# Circuito_Tappingduino_3_Final_-_Conexion.net
KiCad netlist of a schematic drawn in EAGLE
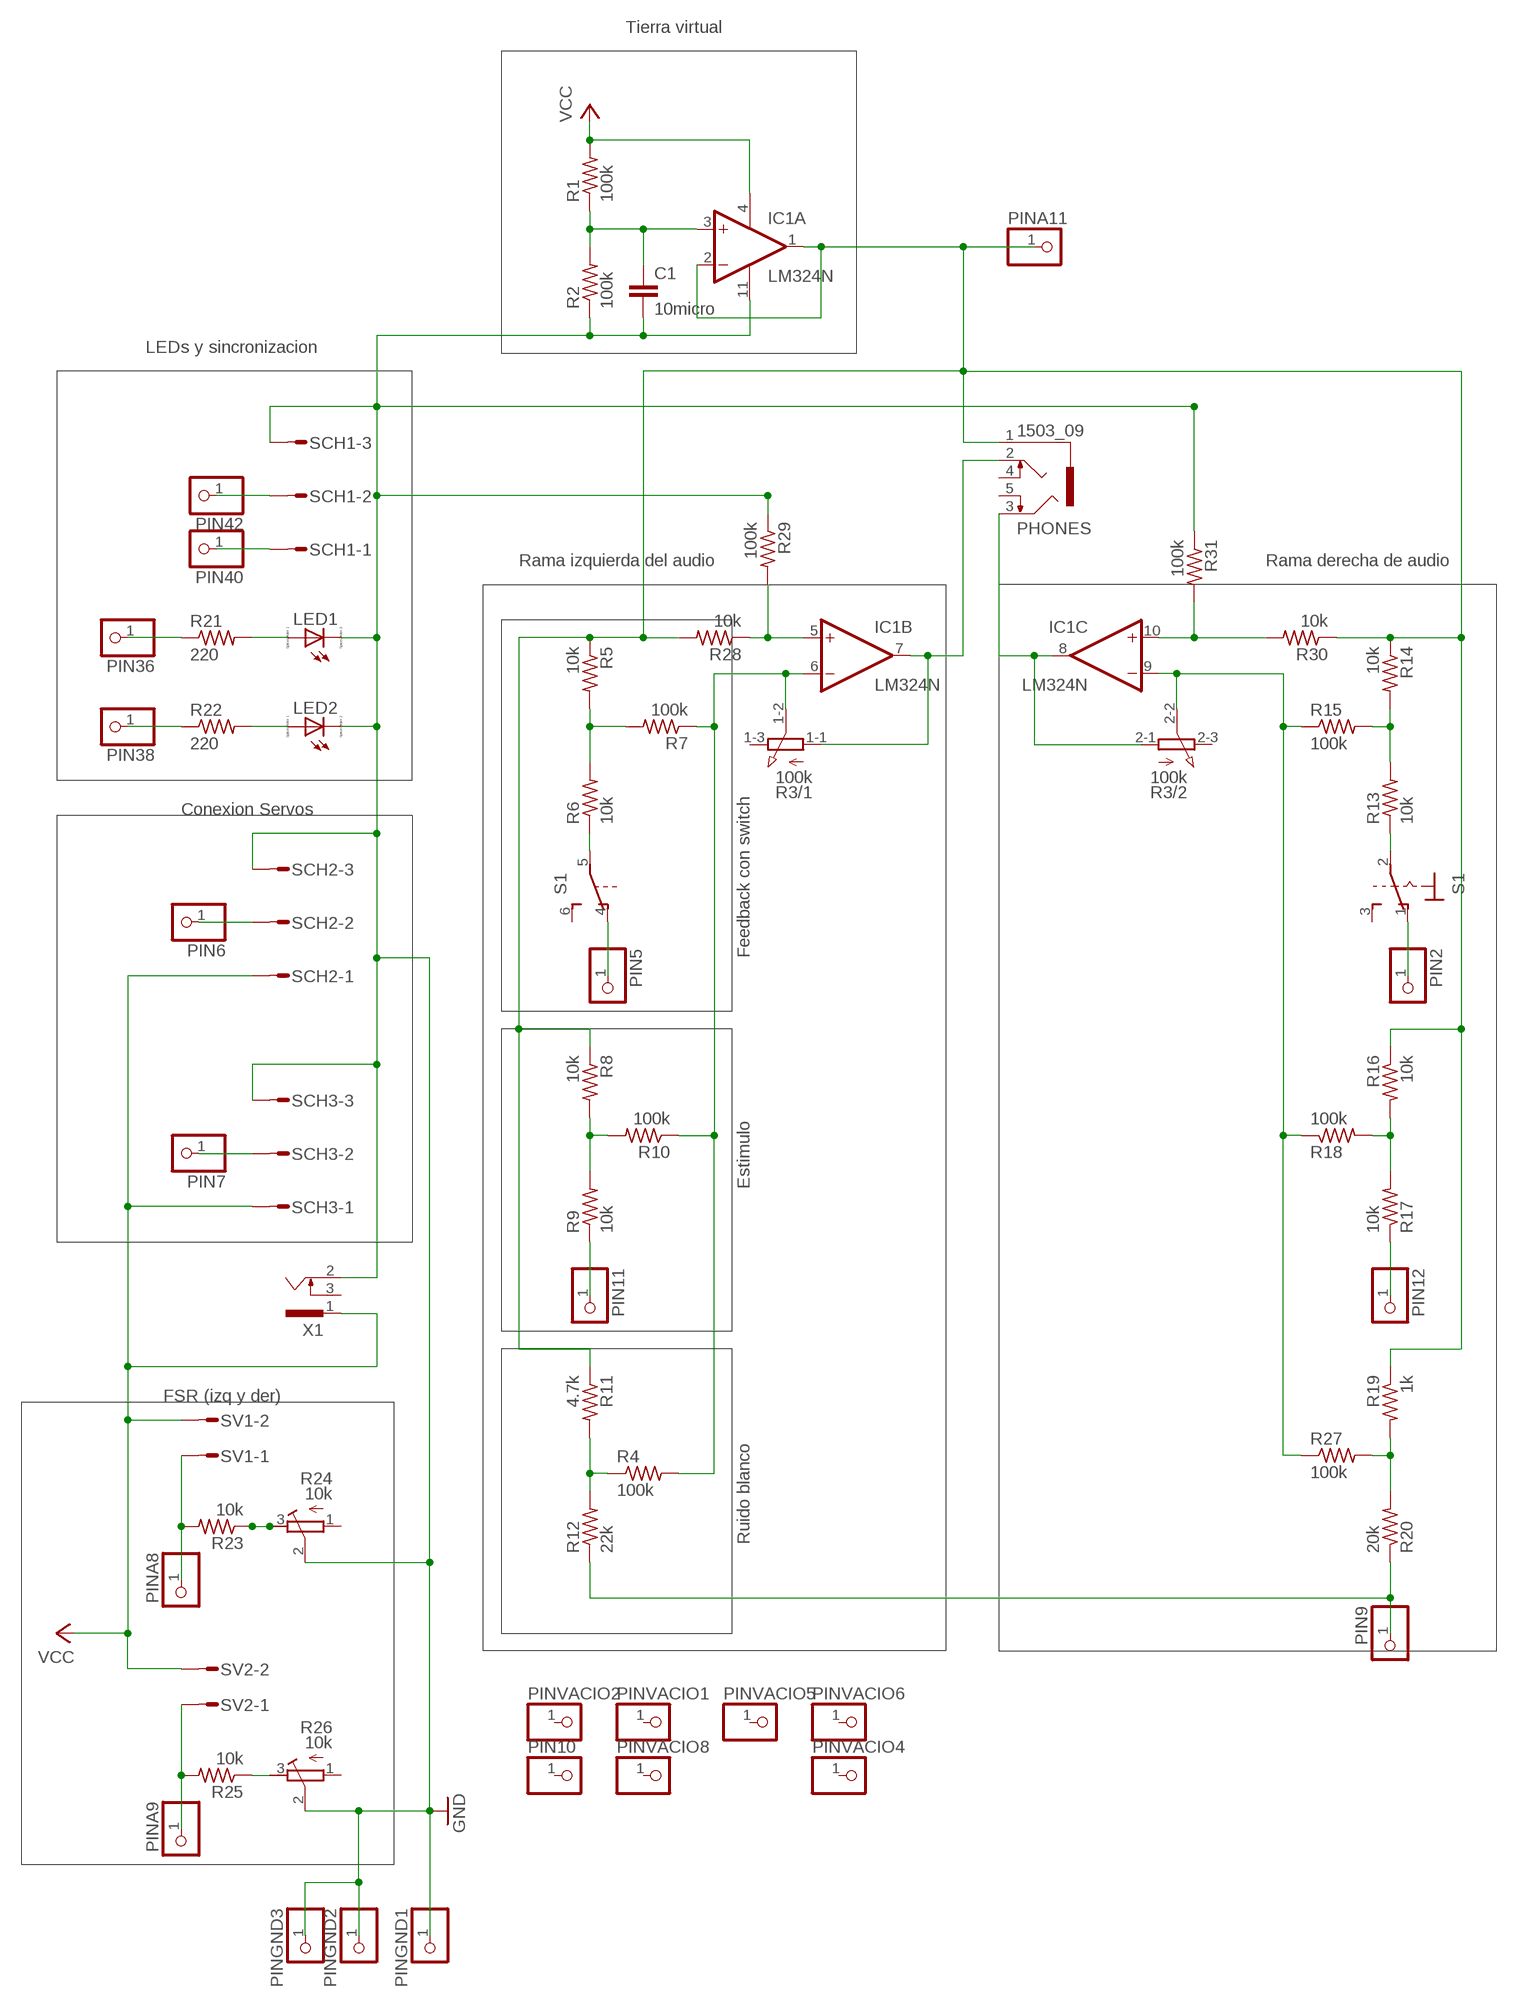
[diagram p0: schematic, sheet 1]

(export (version "E")
  (design (tool "Eeschema 10.0.6"))
  (components
    (comp (ref "C1")
      (value "10micro")
      (footprint "eagle-import:C025-030X050")
      (libsource (lib "eagle-import") (part "C-EU025-030X050"))
    )
    (comp (ref "IC1")
      (value "LM324N")
      (footprint "eagle-import:DIL14")
      (fields (field (name "SPICEPREFIX") "X"))
      (libsource (lib "eagle-import") (part "LM324N"))
    )
    (comp (ref "LED1")
      (value "LED_ELD260")
      (footprint "eagle-import:LED_LD260")
      (fields (field (name "SPICEMODEL") "DMOD"))
      (libsource (lib "eagle-import") (part "LED_ELD260"))
    )
    (comp (ref "LED2")
      (value "LED_ELD260")
      (footprint "eagle-import:LED_LD260")
      (fields (field (name "SPICEMODEL") "DMOD"))
      (libsource (lib "eagle-import") (part "LED_ELD260"))
    )
    (comp (ref "PHONES")
      (value "1503_09")
      (footprint "eagle-import:1503_09")
      (fields (field (name "SPICEPREFIX") "X"))
      (libsource (lib "eagle-import") (part "1503_09"))
    )
    (comp (ref "PIN2")
      (value "PINHD-1X1")
      (footprint "eagle-import:1X01")
      (fields (field (name "SPICEPREFIX") "X"))
      (libsource (lib "eagle-import") (part "PINHD-1X1"))
    )
    (comp (ref "PIN5")
      (value "PINHD-1X1")
      (footprint "eagle-import:1X01")
      (fields (field (name "SPICEPREFIX") "X"))
      (libsource (lib "eagle-import") (part "PINHD-1X1"))
    )
    (comp (ref "PIN6")
      (value "PINHD-1X1")
      (footprint "eagle-import:1X01")
      (fields (field (name "SPICEPREFIX") "X"))
      (libsource (lib "eagle-import") (part "PINHD-1X1"))
    )
    (comp (ref "PIN7")
      (value "PINHD-1X1")
      (footprint "eagle-import:1X01")
      (fields (field (name "SPICEPREFIX") "X"))
      (libsource (lib "eagle-import") (part "PINHD-1X1"))
    )
    (comp (ref "PIN9")
      (value "PINHD-1X1")
      (footprint "eagle-import:1X01")
      (fields (field (name "SPICEPREFIX") "X"))
      (libsource (lib "eagle-import") (part "PINHD-1X1"))
    )
    (comp (ref "PIN10")
      (value "PINHD-1X1")
      (footprint "eagle-import:1X01")
      (fields (field (name "SPICEPREFIX") "X"))
      (libsource (lib "eagle-import") (part "PINHD-1X1"))
    )
    (comp (ref "PIN11")
      (value "PINHD-1X1")
      (footprint "eagle-import:1X01")
      (fields (field (name "SPICEPREFIX") "X"))
      (libsource (lib "eagle-import") (part "PINHD-1X1"))
    )
    (comp (ref "PIN12")
      (value "PINHD-1X1")
      (footprint "eagle-import:1X01")
      (fields (field (name "SPICEPREFIX") "X"))
      (libsource (lib "eagle-import") (part "PINHD-1X1"))
    )
    (comp (ref "PIN36")
      (value "PINHD-1X1")
      (footprint "eagle-import:1X01")
      (fields (field (name "SPICEPREFIX") "X"))
      (libsource (lib "eagle-import") (part "PINHD-1X1"))
    )
    (comp (ref "PIN38")
      (value "PINHD-1X1")
      (footprint "eagle-import:1X01")
      (fields (field (name "SPICEPREFIX") "X"))
      (libsource (lib "eagle-import") (part "PINHD-1X1"))
    )
    (comp (ref "PIN40")
      (value "PINHD-1X1")
      (footprint "eagle-import:1X01")
      (fields (field (name "SPICEPREFIX") "X"))
      (libsource (lib "eagle-import") (part "PINHD-1X1"))
    )
    (comp (ref "PIN42")
      (value "PINHD-1X1")
      (footprint "eagle-import:1X01")
      (fields (field (name "SPICEPREFIX") "X"))
      (libsource (lib "eagle-import") (part "PINHD-1X1"))
    )
    (comp (ref "PINA8")
      (value "PINHD-1X1")
      (footprint "eagle-import:1X01")
      (fields (field (name "SPICEPREFIX") "X"))
      (libsource (lib "eagle-import") (part "PINHD-1X1"))
    )
    (comp (ref "PINA9")
      (value "PINHD-1X1")
      (footprint "eagle-import:1X01")
      (fields (field (name "SPICEPREFIX") "X"))
      (libsource (lib "eagle-import") (part "PINHD-1X1"))
    )
    (comp (ref "PINA11")
      (value "PINHD-1X1")
      (footprint "eagle-import:1X01")
      (fields (field (name "SPICEPREFIX") "X"))
      (libsource (lib "eagle-import") (part "PINHD-1X1"))
    )
    (comp (ref "PINGND1")
      (value "PINHD-1X1")
      (footprint "eagle-import:1X01")
      (fields (field (name "SPICEPREFIX") "X"))
      (libsource (lib "eagle-import") (part "PINHD-1X1"))
    )
    (comp (ref "PINGND2")
      (value "PINHD-1X1")
      (footprint "eagle-import:1X01")
      (fields (field (name "SPICEPREFIX") "X"))
      (libsource (lib "eagle-import") (part "PINHD-1X1"))
    )
    (comp (ref "PINGND3")
      (value "PINHD-1X1")
      (footprint "eagle-import:1X01")
      (fields (field (name "SPICEPREFIX") "X"))
      (libsource (lib "eagle-import") (part "PINHD-1X1"))
    )
    (comp (ref "PINVACIO1")
      (value "PINHD-1X1")
      (footprint "eagle-import:1X01")
      (fields (field (name "SPICEPREFIX") "X"))
      (libsource (lib "eagle-import") (part "PINHD-1X1"))
    )
    (comp (ref "PINVACIO2")
      (value "PINHD-1X1")
      (footprint "eagle-import:1X01")
      (fields (field (name "SPICEPREFIX") "X"))
      (libsource (lib "eagle-import") (part "PINHD-1X1"))
    )
    (comp (ref "PINVACIO4")
      (value "PINHD-1X1")
      (footprint "eagle-import:1X01")
      (fields (field (name "SPICEPREFIX") "X"))
      (libsource (lib "eagle-import") (part "PINHD-1X1"))
    )
    (comp (ref "PINVACIO5")
      (value "PINHD-1X1")
      (footprint "eagle-import:1X01")
      (fields (field (name "SPICEPREFIX") "X"))
      (libsource (lib "eagle-import") (part "PINHD-1X1"))
    )
    (comp (ref "PINVACIO6")
      (value "PINHD-1X1")
      (footprint "eagle-import:1X01")
      (fields (field (name "SPICEPREFIX") "X"))
      (libsource (lib "eagle-import") (part "PINHD-1X1"))
    )
    (comp (ref "PINVACIO8")
      (value "PINHD-1X1")
      (footprint "eagle-import:1X01")
      (fields (field (name "SPICEPREFIX") "X"))
      (libsource (lib "eagle-import") (part "PINHD-1X1"))
    )
    (comp (ref "R1")
      (value "100k")
      (footprint "eagle-import:0207_7")
      (libsource (lib "eagle-import") (part "R-US_0207/7"))
    )
    (comp (ref "R2")
      (value "100k")
      (footprint "eagle-import:0207_7")
      (libsource (lib "eagle-import") (part "R-US_0207/7"))
    )
    (comp (ref "R3")
      (value "100k")
      (footprint "eagle-import:3RP_1610G")
      (fields (field (name "SPICEPREFIX") "J"))
      (libsource (lib "eagle-import") (part "3RP/1610G"))
    )
    (comp (ref "R4")
      (value "100k")
      (footprint "eagle-import:0207_7")
      (libsource (lib "eagle-import") (part "R-US_0207/7"))
    )
    (comp (ref "R5")
      (value "10k")
      (footprint "eagle-import:0207_7")
      (libsource (lib "eagle-import") (part "R-US_0207/7"))
    )
    (comp (ref "R6")
      (value "10k")
      (footprint "eagle-import:0207_7")
      (libsource (lib "eagle-import") (part "R-US_0207/7"))
    )
    (comp (ref "R7")
      (value "100k")
      (footprint "eagle-import:0207_7")
      (libsource (lib "eagle-import") (part "R-US_0207/7"))
    )
    (comp (ref "R8")
      (value "10k")
      (footprint "eagle-import:0207_7")
      (libsource (lib "eagle-import") (part "R-US_0207/7"))
    )
    (comp (ref "R9")
      (value "10k")
      (footprint "eagle-import:0207_7")
      (libsource (lib "eagle-import") (part "R-US_0207/7"))
    )
    (comp (ref "R10")
      (value "100k")
      (footprint "eagle-import:0207_7")
      (libsource (lib "eagle-import") (part "R-US_0207/7"))
    )
    (comp (ref "R11")
      (value "4.7k")
      (footprint "eagle-import:0207_7")
      (libsource (lib "eagle-import") (part "R-US_0207/7"))
    )
    (comp (ref "R12")
      (value "22k")
      (footprint "eagle-import:0207_7")
      (libsource (lib "eagle-import") (part "R-US_0207/7"))
    )
    (comp (ref "R13")
      (value "10k")
      (footprint "eagle-import:0207_7")
      (libsource (lib "eagle-import") (part "R-US_0207/7"))
    )
    (comp (ref "R14")
      (value "10k")
      (footprint "eagle-import:0207_7")
      (libsource (lib "eagle-import") (part "R-US_0207/7"))
    )
    (comp (ref "R15")
      (value "100k")
      (footprint "eagle-import:0207_7")
      (libsource (lib "eagle-import") (part "R-US_0207/7"))
    )
    (comp (ref "R16")
      (value "10k")
      (footprint "eagle-import:0207_7")
      (libsource (lib "eagle-import") (part "R-US_0207/7"))
    )
    (comp (ref "R17")
      (value "10k")
      (footprint "eagle-import:0207_7")
      (libsource (lib "eagle-import") (part "R-US_0207/7"))
    )
    (comp (ref "R18")
      (value "100k")
      (footprint "eagle-import:0207_7")
      (libsource (lib "eagle-import") (part "R-US_0207/7"))
    )
    (comp (ref "R19")
      (value "1k")
      (footprint "eagle-import:0207_7")
      (libsource (lib "eagle-import") (part "R-US_0207/7"))
    )
    (comp (ref "R20")
      (value "20k")
      (footprint "eagle-import:0207_7")
      (libsource (lib "eagle-import") (part "R-US_0207/7"))
    )
    (comp (ref "R21")
      (value "220")
      (footprint "eagle-import:0207_7")
      (libsource (lib "eagle-import") (part "R-US_0207/7"))
    )
    (comp (ref "R22")
      (value "220")
      (footprint "eagle-import:0207_7")
      (libsource (lib "eagle-import") (part "R-US_0207/7"))
    )
    (comp (ref "R23")
      (value "10k")
      (footprint "eagle-import:0207_7")
      (libsource (lib "eagle-import") (part "R-US_0207/7"))
    )
    (comp (ref "R24")
      (value "10k")
      (footprint "eagle-import:RTRIM64W")
      (libsource (lib "eagle-import") (part "R-TRIMM64W"))
    )
    (comp (ref "R25")
      (value "10k")
      (footprint "eagle-import:0207_7")
      (libsource (lib "eagle-import") (part "R-US_0207/7"))
    )
    (comp (ref "R26")
      (value "10k")
      (footprint "eagle-import:RTRIM64W")
      (libsource (lib "eagle-import") (part "R-TRIMM64W"))
    )
    (comp (ref "R27")
      (value "100k")
      (footprint "eagle-import:0207_7")
      (libsource (lib "eagle-import") (part "R-US_0207/7"))
    )
    (comp (ref "R28")
      (value "10k")
      (footprint "eagle-import:0207_7")
      (libsource (lib "eagle-import") (part "R-US_0207/7"))
    )
    (comp (ref "R29")
      (value "100k")
      (footprint "eagle-import:0207_7")
      (libsource (lib "eagle-import") (part "R-US_0207/7"))
    )
    (comp (ref "R30")
      (value "10k")
      (footprint "eagle-import:0207_7")
      (libsource (lib "eagle-import") (part "R-US_0207/7"))
    )
    (comp (ref "R31")
      (value "100k")
      (footprint "eagle-import:0207_7")
      (libsource (lib "eagle-import") (part "R-US_0207/7"))
    )
    (comp (ref "S1")
      (value "320-938")
      (footprint "eagle-import:320-938")
      (libsource (lib "eagle-import") (part "320-938"))
    )
    (comp (ref "SCH1")
      (value "L03P")
      (footprint "eagle-import:L03P")
      (fields (field (name "SPICEPREFIX") "X"))
      (libsource (lib "eagle-import") (part "L03P"))
    )
    (comp (ref "SCH2")
      (value "L03P")
      (footprint "eagle-import:L03P")
      (fields (field (name "SPICEPREFIX") "X"))
      (libsource (lib "eagle-import") (part "L03P"))
    )
    (comp (ref "SCH3")
      (value "L03P")
      (footprint "eagle-import:L03P")
      (fields (field (name "SPICEPREFIX") "X"))
      (libsource (lib "eagle-import") (part "L03P"))
    )
    (comp (ref "SV1")
      (value "L02P")
      (footprint "eagle-import:L02P")
      (fields (field (name "SPICEPREFIX") "X"))
      (libsource (lib "eagle-import") (part "L02P"))
    )
    (comp (ref "SV2")
      (value "L02P")
      (footprint "eagle-import:L02P")
      (fields (field (name "SPICEPREFIX") "X"))
      (libsource (lib "eagle-import") (part "L02P"))
    )
    (comp (ref "X1")
      (value "SCD-014A")
      (footprint "eagle-import:SCD-014-A")
      (fields (field (name "SPICEPREFIX") "X"))
      (libsource (lib "eagle-import") (part "SCD-014A"))
    )
  )
  (nets
    (net (code "1") (name "GND") (class "Default")
      (node (ref "C1") (pin "2") (pinfunction "2_2") (pintype "passive"))
      (node (ref "IC1") (pin "11") (pinfunction "V-_11") (pintype "power_in"))
      (node (ref "LED1") (pin "K") (pinfunction "C_K") (pintype "passive"))
      (node (ref "LED2") (pin "K") (pinfunction "C_K") (pintype "passive"))
      (node (ref "PINGND1") (pin "1") (pinfunction "1_1") (pintype "passive"))
      (node (ref "PINGND2") (pin "1") (pinfunction "1_1") (pintype "passive"))
      (node (ref "PINGND3") (pin "1") (pinfunction "1_1") (pintype "passive"))
      (node (ref "R2") (pin "1") (pinfunction "1_1") (pintype "passive"))
      (node (ref "R24") (pin "2") (pinfunction "S_2") (pintype "passive"))
      (node (ref "R26") (pin "2") (pinfunction "S_2") (pintype "passive"))
      (node (ref "R29") (pin "1") (pinfunction "1_1") (pintype "passive"))
      (node (ref "R31") (pin "1") (pinfunction "1_1") (pintype "passive"))
      (node (ref "SCH1") (pin "3") (pinfunction "S_3") (pintype "passive"))
      (node (ref "SCH2") (pin "3") (pinfunction "S_3") (pintype "passive"))
      (node (ref "SCH3") (pin "3") (pinfunction "S_3") (pintype "passive"))
      (node (ref "X1") (pin "2") (pinfunction "2_2") (pintype "passive"))
    )
    (net (code "2") (name "Net-(IC1A-+IN)") (class "Default")
      (node (ref "C1") (pin "1") (pinfunction "1_1") (pintype "passive"))
      (node (ref "IC1") (pin "3") (pinfunction "+IN_3") (pintype "input"))
      (node (ref "R1") (pin "1") (pinfunction "1_1") (pintype "passive"))
      (node (ref "R2") (pin "2") (pinfunction "2_2") (pintype "passive"))
    )
    (net (code "3") (name "Net-(IC1A--IN)") (class "Default")
      (node (ref "IC1") (pin "1") (pinfunction "OUT_1") (pintype "output"))
      (node (ref "IC1") (pin "2") (pinfunction "-IN_2") (pintype "input"))
      (node (ref "PHONES") (pin "1") (pinfunction "1_1") (pintype "passive"))
      (node (ref "PINA11") (pin "1") (pinfunction "1_1") (pintype "passive"))
      (node (ref "R11") (pin "1") (pinfunction "1_1") (pintype "passive"))
      (node (ref "R14") (pin "1") (pinfunction "1_1") (pintype "passive"))
      (node (ref "R16") (pin "1") (pinfunction "1_1") (pintype "passive"))
      (node (ref "R19") (pin "1") (pinfunction "1_1") (pintype "passive"))
      (node (ref "R28") (pin "2") (pinfunction "2_2") (pintype "passive"))
      (node (ref "R30") (pin "1") (pinfunction "1_1") (pintype "passive"))
      (node (ref "R5") (pin "1") (pinfunction "1_1") (pintype "passive"))
      (node (ref "R8") (pin "1") (pinfunction "1_1") (pintype "passive"))
    )
    (net (code "4") (name "Net-(IC1B-+IN)") (class "Default")
      (node (ref "IC1") (pin "5") (pinfunction "+IN_5") (pintype "input"))
      (node (ref "R28") (pin "1") (pinfunction "1_1") (pintype "passive"))
      (node (ref "R29") (pin "2") (pinfunction "2_2") (pintype "passive"))
    )
    (net (code "5") (name "Net-(IC1B--IN)") (class "Default")
      (node (ref "IC1") (pin "6") (pinfunction "-IN_6") (pintype "input"))
      (node (ref "R10") (pin "1") (pinfunction "1_1") (pintype "passive"))
      (node (ref "R3") (pin "1-2") (pinfunction "S_1-2") (pintype "passive"))
      (node (ref "R4") (pin "2") (pinfunction "2_2") (pintype "passive"))
      (node (ref "R7") (pin "1") (pinfunction "1_1") (pintype "passive"))
    )
    (net (code "6") (name "Net-(IC1B-OUT)") (class "Default")
      (node (ref "IC1") (pin "7") (pinfunction "OUT_7") (pintype "output"))
      (node (ref "PHONES") (pin "2") (pinfunction "2_2") (pintype "passive"))
      (node (ref "R3") (pin "1-1") (pinfunction "A_1-1") (pintype "passive"))
    )
    (net (code "7") (name "Net-(IC1C-+IN)") (class "Default")
      (node (ref "IC1") (pin "10") (pinfunction "+IN_10") (pintype "input"))
      (node (ref "R30") (pin "2") (pinfunction "2_2") (pintype "passive"))
      (node (ref "R31") (pin "2") (pinfunction "2_2") (pintype "passive"))
    )
    (net (code "8") (name "Net-(IC1C--IN)") (class "Default")
      (node (ref "IC1") (pin "9") (pinfunction "-IN_9") (pintype "input"))
      (node (ref "R15") (pin "1") (pinfunction "1_1") (pintype "passive"))
      (node (ref "R18") (pin "1") (pinfunction "1_1") (pintype "passive"))
      (node (ref "R27") (pin "1") (pinfunction "1_1") (pintype "passive"))
      (node (ref "R3") (pin "2-2") (pinfunction "S_2-2") (pintype "passive"))
    )
    (net (code "9") (name "Net-(IC1C-OUT)") (class "Default")
      (node (ref "IC1") (pin "8") (pinfunction "OUT_8") (pintype "output"))
      (node (ref "PHONES") (pin "3") (pinfunction "3_3") (pintype "passive"))
      (node (ref "R3") (pin "2-1") (pinfunction "A_2-1") (pintype "passive"))
    )
    (net (code "10") (name "Net-(LED1-PadA)") (class "Default")
      (node (ref "LED1") (pin "A") (pinfunction "A_A") (pintype "passive"))
      (node (ref "R21") (pin "2") (pinfunction "2_2") (pintype "passive"))
    )
    (net (code "11") (name "Net-(LED2-PadA)") (class "Default")
      (node (ref "LED2") (pin "A") (pinfunction "A_A") (pintype "passive"))
      (node (ref "R22") (pin "2") (pinfunction "2_2") (pintype "passive"))
    )
    (net (code "12") (name "Net-(PIN9-Pad1)") (class "Default")
      (node (ref "PIN9") (pin "1") (pinfunction "1_1") (pintype "passive"))
      (node (ref "R12") (pin "1") (pinfunction "1_1") (pintype "passive"))
      (node (ref "R20") (pin "1") (pinfunction "1_1") (pintype "passive"))
    )
    (net (code "13") (name "Net-(PIN11-Pad1)") (class "Default")
      (node (ref "PIN11") (pin "1") (pinfunction "1_1") (pintype "passive"))
      (node (ref "R9") (pin "1") (pinfunction "1_1") (pintype "passive"))
    )
    (net (code "14") (name "Net-(PIN12-Pad1)") (class "Default")
      (node (ref "PIN12") (pin "1") (pinfunction "1_1") (pintype "passive"))
      (node (ref "R17") (pin "1") (pinfunction "1_1") (pintype "passive"))
    )
    (net (code "15") (name "Net-(PIN36-Pad1)") (class "Default")
      (node (ref "PIN36") (pin "1") (pinfunction "1_1") (pintype "passive"))
      (node (ref "R21") (pin "1") (pinfunction "1_1") (pintype "passive"))
    )
    (net (code "16") (name "Net-(PIN38-Pad1)") (class "Default")
      (node (ref "PIN38") (pin "1") (pinfunction "1_1") (pintype "passive"))
      (node (ref "R22") (pin "1") (pinfunction "1_1") (pintype "passive"))
    )
    (net (code "17") (name "Net-(R5-Pad2)") (class "Default")
      (node (ref "R5") (pin "2") (pinfunction "2_2") (pintype "passive"))
      (node (ref "R6") (pin "2") (pinfunction "2_2") (pintype "passive"))
      (node (ref "R7") (pin "2") (pinfunction "2_2") (pintype "passive"))
    )
    (net (code "18") (name "Net-(R10-Pad2)") (class "Default")
      (node (ref "R10") (pin "2") (pinfunction "2_2") (pintype "passive"))
      (node (ref "R8") (pin "2") (pinfunction "2_2") (pintype "passive"))
      (node (ref "R9") (pin "2") (pinfunction "2_2") (pintype "passive"))
    )
    (net (code "19") (name "Net-(R11-Pad2)") (class "Default")
      (node (ref "R11") (pin "2") (pinfunction "2_2") (pintype "passive"))
      (node (ref "R12") (pin "2") (pinfunction "2_2") (pintype "passive"))
      (node (ref "R4") (pin "1") (pinfunction "1_1") (pintype "passive"))
    )
    (net (code "20") (name "Net-(R13-Pad2)") (class "Default")
      (node (ref "R13") (pin "2") (pinfunction "2_2") (pintype "passive"))
      (node (ref "R14") (pin "2") (pinfunction "2_2") (pintype "passive"))
      (node (ref "R15") (pin "2") (pinfunction "2_2") (pintype "passive"))
    )
    (net (code "21") (name "Net-(R16-Pad2)") (class "Default")
      (node (ref "R16") (pin "2") (pinfunction "2_2") (pintype "passive"))
      (node (ref "R17") (pin "2") (pinfunction "2_2") (pintype "passive"))
      (node (ref "R18") (pin "2") (pinfunction "2_2") (pintype "passive"))
    )
    (net (code "22") (name "Net-(R19-Pad2)") (class "Default")
      (node (ref "R19") (pin "2") (pinfunction "2_2") (pintype "passive"))
      (node (ref "R20") (pin "2") (pinfunction "2_2") (pintype "passive"))
      (node (ref "R27") (pin "2") (pinfunction "2_2") (pintype "passive"))
    )
    (net (code "23") (name "Net-(R24-E)") (class "Default")
      (node (ref "R23") (pin "1") (pinfunction "1_1") (pintype "passive"))
      (node (ref "R24") (pin "3") (pinfunction "E_3") (pintype "passive"))
    )
    (net (code "24") (name "Net-(R26-E)") (class "Default")
      (node (ref "R25") (pin "1") (pinfunction "1_1") (pintype "passive"))
      (node (ref "R26") (pin "3") (pinfunction "E_3") (pintype "passive"))
    )
    (net (code "25") (name "Net-(S1A-O)") (class "Default")
      (node (ref "PIN2") (pin "1") (pinfunction "1_1") (pintype "passive"))
      (node (ref "S1") (pin "1") (pinfunction "O_1") (pintype "passive"))
    )
    (net (code "26") (name "Net-(S1A-P)") (class "Default")
      (node (ref "R13") (pin "1") (pinfunction "1_1") (pintype "passive"))
      (node (ref "S1") (pin "2") (pinfunction "P_2") (pintype "passive"))
    )
    (net (code "27") (name "Net-(S1B-O)") (class "Default")
      (node (ref "PIN5") (pin "1") (pinfunction "1_1") (pintype "passive"))
      (node (ref "S1") (pin "4") (pinfunction "O_4") (pintype "passive"))
    )
    (net (code "28") (name "Net-(S1B-P)") (class "Default")
      (node (ref "R6") (pin "1") (pinfunction "1_1") (pintype "passive"))
      (node (ref "S1") (pin "5") (pinfunction "P_5") (pintype "passive"))
    )
    (net (code "29") (name "Net-(SCH1A-S)") (class "Default")
      (node (ref "PIN40") (pin "1") (pinfunction "1_1") (pintype "passive"))
      (node (ref "SCH1") (pin "1") (pinfunction "S_1") (pintype "passive"))
    )
    (net (code "30") (name "Net-(SCH1B-S)") (class "Default")
      (node (ref "PIN42") (pin "1") (pinfunction "1_1") (pintype "passive"))
      (node (ref "SCH1") (pin "2") (pinfunction "S_2") (pintype "passive"))
    )
    (net (code "31") (name "Net-(SCH2B-S)") (class "Default")
      (node (ref "PIN6") (pin "1") (pinfunction "1_1") (pintype "passive"))
      (node (ref "SCH2") (pin "2") (pinfunction "S_2") (pintype "passive"))
    )
    (net (code "32") (name "Net-(SCH3B-S)") (class "Default")
      (node (ref "PIN7") (pin "1") (pinfunction "1_1") (pintype "passive"))
      (node (ref "SCH3") (pin "2") (pinfunction "S_2") (pintype "passive"))
    )
    (net (code "33") (name "Net-(SV1A-S)") (class "Default")
      (node (ref "PINA8") (pin "1") (pinfunction "1_1") (pintype "passive"))
      (node (ref "R23") (pin "2") (pinfunction "2_2") (pintype "passive"))
      (node (ref "SV1") (pin "1") (pinfunction "S_1") (pintype "passive"))
    )
    (net (code "34") (name "Net-(SV2A-S)") (class "Default")
      (node (ref "PINA9") (pin "1") (pinfunction "1_1") (pintype "passive"))
      (node (ref "R25") (pin "2") (pinfunction "2_2") (pintype "passive"))
      (node (ref "SV2") (pin "1") (pinfunction "S_1") (pintype "passive"))
    )
    (net (code "35") (name "VCC") (class "Default")
      (node (ref "IC1") (pin "4") (pinfunction "V+_4") (pintype "power_in"))
      (node (ref "R1") (pin "2") (pinfunction "2_2") (pintype "passive"))
      (node (ref "SCH2") (pin "1") (pinfunction "S_1") (pintype "passive"))
      (node (ref "SCH3") (pin "1") (pinfunction "S_1") (pintype "passive"))
      (node (ref "SV1") (pin "2") (pinfunction "S_2") (pintype "passive"))
      (node (ref "SV2") (pin "2") (pinfunction "S_2") (pintype "passive"))
      (node (ref "X1") (pin "1") (pinfunction "1_1") (pintype "passive"))
    )
    (net (code "36") (name "unconnected-(PHONES-Pad4)") (class "Default")
      (node (ref "PHONES") (pin "4") (pinfunction "4_4") (pintype "passive"))
    )
    (net (code "37") (name "unconnected-(PHONES-Pad5)") (class "Default")
      (node (ref "PHONES") (pin "5") (pinfunction "5_5") (pintype "passive"))
    )
    (net (code "38") (name "unconnected-(PIN10-Pad1)") (class "Default")
      (node (ref "PIN10") (pin "1") (pinfunction "1_1") (pintype "passive"))
    )
    (net (code "39") (name "unconnected-(PINVACIO1-Pad1)") (class "Default")
      (node (ref "PINVACIO1") (pin "1") (pinfunction "1_1") (pintype "passive"))
    )
    (net (code "40") (name "unconnected-(PINVACIO2-Pad1)") (class "Default")
      (node (ref "PINVACIO2") (pin "1") (pinfunction "1_1") (pintype "passive"))
    )
    (net (code "41") (name "unconnected-(PINVACIO4-Pad1)") (class "Default")
      (node (ref "PINVACIO4") (pin "1") (pinfunction "1_1") (pintype "passive"))
    )
    (net (code "42") (name "unconnected-(PINVACIO5-Pad1)") (class "Default")
      (node (ref "PINVACIO5") (pin "1") (pinfunction "1_1") (pintype "passive"))
    )
    (net (code "43") (name "unconnected-(PINVACIO6-Pad1)") (class "Default")
      (node (ref "PINVACIO6") (pin "1") (pinfunction "1_1") (pintype "passive"))
    )
    (net (code "44") (name "unconnected-(PINVACIO8-Pad1)") (class "Default")
      (node (ref "PINVACIO8") (pin "1") (pinfunction "1_1") (pintype "passive"))
    )
    (net (code "45") (name "unconnected-(R3A-E-Pad1-3)") (class "Default")
      (node (ref "R3") (pin "1-3") (pinfunction "E_1-3") (pintype "passive"))
    )
    (net (code "46") (name "unconnected-(R3B-E-Pad2-3)") (class "Default")
      (node (ref "R3") (pin "2-3") (pinfunction "E_2-3") (pintype "passive"))
    )
    (net (code "47") (name "unconnected-(R24-A-Pad1)") (class "Default")
      (node (ref "R24") (pin "1") (pinfunction "A_1") (pintype "passive"))
    )
    (net (code "48") (name "unconnected-(R26-A-Pad1)") (class "Default")
      (node (ref "R26") (pin "1") (pinfunction "A_1") (pintype "passive"))
    )
    (net (code "49") (name "unconnected-(S1A-S-Pad3)") (class "Default")
      (node (ref "S1") (pin "3") (pinfunction "S_3") (pintype "passive"))
    )
    (net (code "50") (name "unconnected-(S1B-S-Pad6)") (class "Default")
      (node (ref "S1") (pin "6") (pinfunction "S_6") (pintype "passive"))
    )
    (net (code "51") (name "unconnected-(X1-Pad3)") (class "Default")
      (node (ref "X1") (pin "3") (pinfunction "3_3") (pintype "passive"))
    )
  )
)
